# NOT_Gate.net
KiCad netlist of a schematic drawn in EAGLE
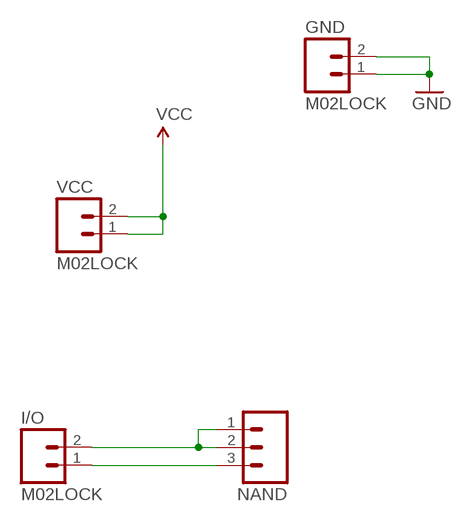
[diagram p0: schematic, sheet 1]

(export (version "E")
  (design (tool "Eeschema 10.0.6"))
  (components
    (comp (ref "GND")
      (value "M02LOCK")
      (footprint "eagle-import:1X02_LOCK")
      (libsource (lib "eagle-import") (part "M02LOCK"))
    )
    (comp (ref "I/O")
      (value "M02LOCK")
      (footprint "eagle-import:1X02_LOCK")
      (libsource (lib "eagle-import") (part "M02LOCK"))
    )
    (comp (ref "NAND")
      (value "M03LOCK")
      (footprint "eagle-import:1X03_LOCK")
      (libsource (lib "eagle-import") (part "M03LOCK"))
    )
    (comp (ref "VCC")
      (value "M02LOCK")
      (footprint "eagle-import:1X02_LOCK")
      (libsource (lib "eagle-import") (part "M02LOCK"))
    )
  )
  (nets
    (net (code "1") (name "GND") (class "Default")
      (node (ref "GND") (pin "1") (pinfunction "1_1") (pintype "passive"))
      (node (ref "GND") (pin "2") (pinfunction "2_2") (pintype "passive"))
    )
    (net (code "2") (name "Net-(I/O-Pad1)") (class "Default")
      (node (ref "I/O") (pin "1") (pinfunction "1_1") (pintype "passive"))
      (node (ref "NAND") (pin "3") (pinfunction "3_3") (pintype "passive"))
    )
    (net (code "3") (name "Net-(I/O-Pad2)") (class "Default")
      (node (ref "I/O") (pin "2") (pinfunction "2_2") (pintype "passive"))
      (node (ref "NAND") (pin "1") (pinfunction "1_1") (pintype "passive"))
      (node (ref "NAND") (pin "2") (pinfunction "2_2") (pintype "passive"))
    )
    (net (code "4") (name "VCC") (class "Default")
      (node (ref "VCC") (pin "1") (pinfunction "1_1") (pintype "passive"))
      (node (ref "VCC") (pin "2") (pinfunction "2_2") (pintype "passive"))
    )
  )
)
